# EAGLE_9_X-Piclodio3.net
KiCad netlist of a schematic drawn in EAGLE
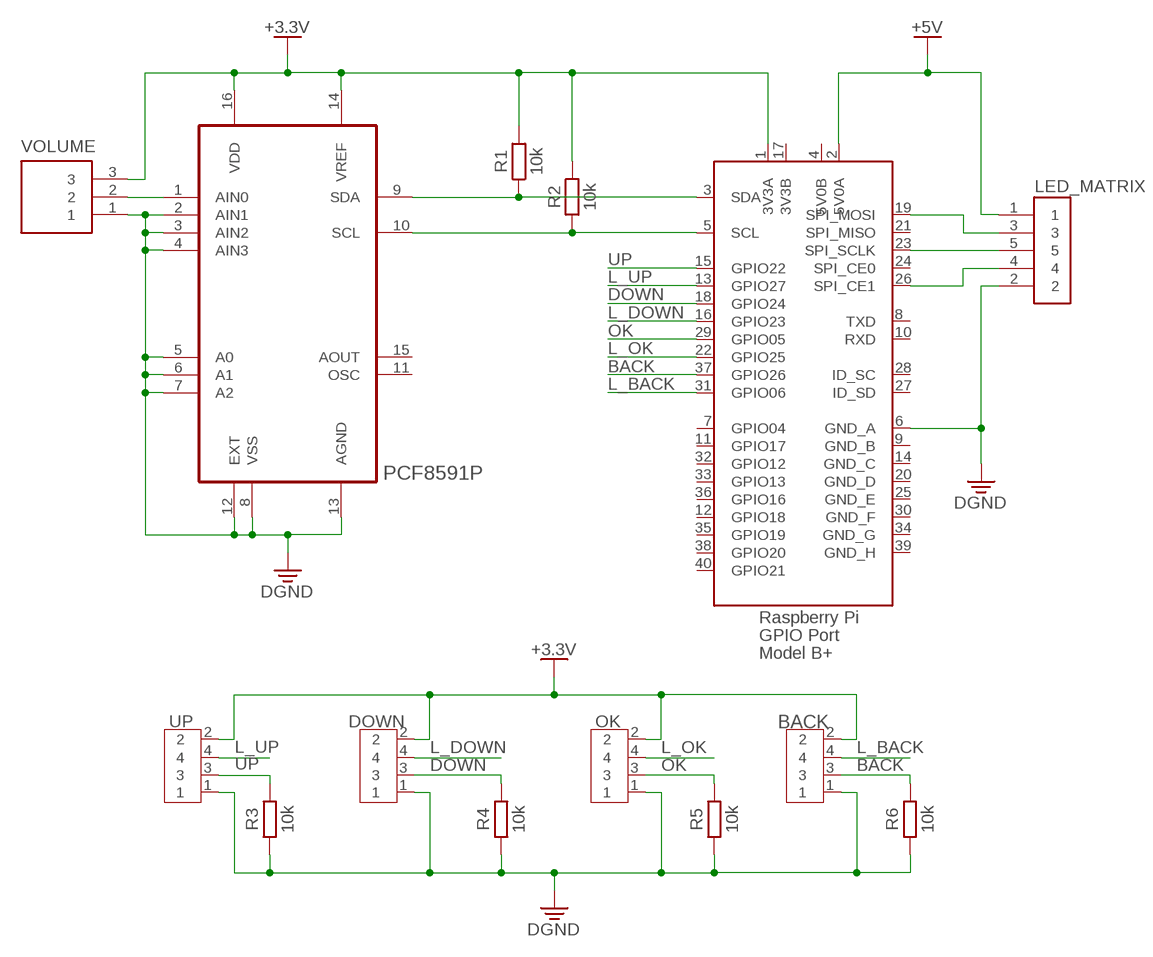
[diagram p0: schematic, sheet 1]

(export (version "E")
  (design (tool "Eeschema 10.0.6"))
  (components
    (comp (ref "BACK")
      (value "3A/250V")
      (footprint "eagle-import:B4B-XH-A")
      (fields (field (name "MANUFACTURER") "JST (XH connector)") (field (name "MPN") "B4B-XH-A"))
      (libsource (lib "eagle-import") (part "B4B-XH-A"))
    )
    (comp (ref "DOWN")
      (value "3A/250V")
      (footprint "eagle-import:B4B-XH-A")
      (fields (field (name "MANUFACTURER") "JST (XH connector)") (field (name "MPN") "B4B-XH-A"))
      (libsource (lib "eagle-import") (part "B4B-XH-A"))
    )
    (comp (ref "LED_MATRIX")
      (value "S5B-XH-A(LF)(SN)")
      (footprint "eagle-import:JST_S5B-XH-A(LF)(SN)")
      (fields (field (name "MANUFACTURER") "JST"))
      (libsource (lib "eagle-import") (part "S5B-XH-A(LF)(SN)"))
    )
    (comp (ref "OK")
      (value "3A/250V")
      (footprint "eagle-import:B4B-XH-A")
      (fields (field (name "MANUFACTURER") "JST (XH connector)") (field (name "MPN") "B4B-XH-A"))
      (libsource (lib "eagle-import") (part "B4B-XH-A"))
    )
    (comp (ref "R1")
      (value "10k")
      (footprint "eagle-import:RESAD1176W63L850D250B")
      (libsource (lib "eagle-import") (part "RAXIAL-11.7MM-PITCH_"))
    )
    (comp (ref "R2")
      (value "10k")
      (footprint "eagle-import:RESAD1176W63L850D250B")
      (libsource (lib "eagle-import") (part "RAXIAL-11.7MM-PITCH_"))
    )
    (comp (ref "R3")
      (value "10k")
      (footprint "eagle-import:RESAD1176W63L850D250B")
      (libsource (lib "eagle-import") (part "RAXIAL-11.7MM-PITCH_"))
    )
    (comp (ref "R4")
      (value "10k")
      (footprint "eagle-import:RESAD1176W63L850D250B")
      (libsource (lib "eagle-import") (part "RAXIAL-11.7MM-PITCH_"))
    )
    (comp (ref "R5")
      (value "10k")
      (footprint "eagle-import:RESAD1176W63L850D250B")
      (libsource (lib "eagle-import") (part "RAXIAL-11.7MM-PITCH_"))
    )
    (comp (ref "R6")
      (value "10k")
      (footprint "eagle-import:RESAD1176W63L850D250B")
      (libsource (lib "eagle-import") (part "RAXIAL-11.7MM-PITCH_"))
    )
    (comp (ref "U2")
      (value "PCF8591P")
      (footprint "eagle-import:DIP254P762X420-16")
      (fields (field (name "MF") "NXP USA"))
      (libsource (lib "eagle-import") (part "PCF8591P"))
    )
    (comp (ref "UP")
      (value "3A/250V")
      (footprint "eagle-import:B4B-XH-A")
      (fields
        (field (name "MANUFACTURER") "JST (XH connector)")
        (field (name "MPN") "B4B-XH-A")
        (field (name "SPICEPREFIX") "E")
      )
      (libsource (lib "eagle-import") (part "B4B-XH-A"))
    )
    (comp (ref "VOLUME")
      (value "S3B-XH-A(LF)(SN)")
      (footprint "eagle-import:JST_S3B-XH-A(LF)(SN)")
      (fields (field (name "MANUFACTURER") "JST"))
      (libsource (lib "eagle-import") (part "S3B-XH-A(LF)(SN)"))
    )
    (comp (ref "X1")
      (value "RASPI_BOARD_B+#_H")
      (footprint "eagle-import:RASPI_BOARD_B+HAT")
      (libsource (lib "eagle-import") (part "RASPI_BOARD_B+#_H"))
    )
  )
  (nets
    (net (code "1") (name "+3.3V") (class "Default")
      (node (ref "BACK") (pin "2") (pinfunction "2_2") (pintype "bidirectional"))
      (node (ref "DOWN") (pin "2") (pinfunction "2_2") (pintype "bidirectional"))
      (node (ref "OK") (pin "2") (pinfunction "2_2") (pintype "bidirectional"))
      (node (ref "R1") (pin "2") (pinfunction "2_2") (pintype "passive"))
      (node (ref "R2") (pin "1") (pinfunction "1_1") (pintype "passive"))
      (node (ref "U2") (pin "14") (pinfunction "VREF_14") (pintype "input"))
      (node (ref "U2") (pin "16") (pinfunction "VDD_16") (pintype "power_in"))
      (node (ref "UP") (pin "2") (pinfunction "2_2") (pintype "bidirectional"))
      (node (ref "VOLUME") (pin "3") (pinfunction "3_3") (pintype "passive"))
      (node (ref "X1") (pin "1") (pinfunction "3V3A_1") (pintype "power_in"))
    )
    (net (code "2") (name "+5V") (class "Default")
      (node (ref "LED_MATRIX") (pin "1") (pinfunction "1_1") (pintype "passive"))
      (node (ref "X1") (pin "2") (pinfunction "5V0A_2") (pintype "power_in"))
    )
    (net (code "3") (name "/BACK") (class "Default")
      (node (ref "BACK") (pin "3") (pinfunction "3_3") (pintype "bidirectional"))
      (node (ref "R6") (pin "2") (pinfunction "2_2") (pintype "passive"))
      (node (ref "X1") (pin "37") (pinfunction "GPIO26_37") (pintype "input"))
    )
    (net (code "4") (name "/DOWN") (class "Default")
      (node (ref "DOWN") (pin "3") (pinfunction "3_3") (pintype "bidirectional"))
      (node (ref "R4") (pin "2") (pinfunction "2_2") (pintype "passive"))
      (node (ref "X1") (pin "18") (pinfunction "GPIO24_18") (pintype "input"))
    )
    (net (code "5") (name "/L_BACK") (class "Default")
      (node (ref "BACK") (pin "4") (pinfunction "4_4") (pintype "bidirectional"))
      (node (ref "X1") (pin "31") (pinfunction "GPIO06_31") (pintype "output"))
    )
    (net (code "6") (name "/L_DOWN") (class "Default")
      (node (ref "DOWN") (pin "4") (pinfunction "4_4") (pintype "bidirectional"))
      (node (ref "X1") (pin "16") (pinfunction "GPIO23_16") (pintype "output"))
    )
    (net (code "7") (name "/L_OK") (class "Default")
      (node (ref "OK") (pin "4") (pinfunction "4_4") (pintype "bidirectional"))
      (node (ref "X1") (pin "22") (pinfunction "GPIO25_22") (pintype "output"))
    )
    (net (code "8") (name "/L_UP") (class "Default")
      (node (ref "UP") (pin "4") (pinfunction "4_4") (pintype "bidirectional"))
      (node (ref "X1") (pin "13") (pinfunction "GPIO27_13") (pintype "output"))
    )
    (net (code "9") (name "/OK") (class "Default")
      (node (ref "OK") (pin "3") (pinfunction "3_3") (pintype "bidirectional"))
      (node (ref "R5") (pin "2") (pinfunction "2_2") (pintype "passive"))
      (node (ref "X1") (pin "29") (pinfunction "GPIO05_29") (pintype "input"))
    )
    (net (code "10") (name "/UP") (class "Default")
      (node (ref "R3") (pin "2") (pinfunction "2_2") (pintype "passive"))
      (node (ref "UP") (pin "3") (pinfunction "3_3") (pintype "bidirectional"))
      (node (ref "X1") (pin "15") (pinfunction "GPIO22_15") (pintype "input"))
    )
    (net (code "11") (name "DGND") (class "Default")
      (node (ref "BACK") (pin "1") (pinfunction "1_1") (pintype "bidirectional"))
      (node (ref "DOWN") (pin "1") (pinfunction "1_1") (pintype "bidirectional"))
      (node (ref "LED_MATRIX") (pin "2") (pinfunction "2_2") (pintype "passive"))
      (node (ref "OK") (pin "1") (pinfunction "1_1") (pintype "bidirectional"))
      (node (ref "R3") (pin "1") (pinfunction "1_1") (pintype "passive"))
      (node (ref "R4") (pin "1") (pinfunction "1_1") (pintype "passive"))
      (node (ref "R5") (pin "1") (pinfunction "1_1") (pintype "passive"))
      (node (ref "R6") (pin "1") (pinfunction "1_1") (pintype "passive"))
      (node (ref "U2") (pin "12") (pinfunction "EXT_12") (pintype "input"))
      (node (ref "U2") (pin "13") (pinfunction "AGND_13") (pintype "power_in"))
      (node (ref "U2") (pin "2") (pinfunction "AIN1_2") (pintype "input"))
      (node (ref "U2") (pin "3") (pinfunction "AIN2_3") (pintype "input"))
      (node (ref "U2") (pin "4") (pinfunction "AIN3_4") (pintype "input"))
      (node (ref "U2") (pin "5") (pinfunction "A0_5") (pintype "input"))
      (node (ref "U2") (pin "6") (pinfunction "A1_6") (pintype "input"))
      (node (ref "U2") (pin "7") (pinfunction "A2_7") (pintype "input"))
      (node (ref "U2") (pin "8") (pinfunction "VSS_8") (pintype "input"))
      (node (ref "UP") (pin "1") (pinfunction "1_1") (pintype "bidirectional"))
      (node (ref "VOLUME") (pin "1") (pinfunction "1_1") (pintype "passive"))
      (node (ref "X1") (pin "6") (pinfunction "GND_A_6") (pintype "power_in"))
    )
    (net (code "12") (name "Net-(U2-AIN0)") (class "Default")
      (node (ref "U2") (pin "1") (pinfunction "AIN0_1") (pintype "input"))
      (node (ref "VOLUME") (pin "2") (pinfunction "2_2") (pintype "passive"))
    )
    (net (code "13") (name "Net-(U2-SCL)") (class "Default")
      (node (ref "R2") (pin "2") (pinfunction "2_2") (pintype "passive"))
      (node (ref "U2") (pin "10") (pinfunction "SCL_10") (pintype "input"))
      (node (ref "X1") (pin "5") (pinfunction "SCL_5") (pintype "bidirectional"))
    )
    (net (code "14") (name "Net-(U2-SDA)") (class "Default")
      (node (ref "R1") (pin "1") (pinfunction "1_1") (pintype "passive"))
      (node (ref "U2") (pin "9") (pinfunction "SDA_9") (pintype "bidirectional"))
      (node (ref "X1") (pin "3") (pinfunction "SDA_3") (pintype "bidirectional"))
    )
    (net (code "15") (name "Net-(X1-SPI_CE1)") (class "Default")
      (node (ref "LED_MATRIX") (pin "4") (pinfunction "4_4") (pintype "passive"))
      (node (ref "X1") (pin "26") (pinfunction "SPI_CE1_26") (pintype "bidirectional"))
    )
    (net (code "16") (name "Net-(X1-SPI_MOSI)") (class "Default")
      (node (ref "LED_MATRIX") (pin "3") (pinfunction "3_3") (pintype "passive"))
      (node (ref "X1") (pin "19") (pinfunction "SPI_MOSI_19") (pintype "bidirectional"))
    )
    (net (code "17") (name "Net-(X1-SPI_SCLK)") (class "Default")
      (node (ref "LED_MATRIX") (pin "5") (pinfunction "5_5") (pintype "passive"))
      (node (ref "X1") (pin "23") (pinfunction "SPI_SCLK_23") (pintype "bidirectional"))
    )
    (net (code "18") (name "unconnected-(U2-AOUT-Pad15)") (class "Default")
      (node (ref "U2") (pin "15") (pinfunction "AOUT_15") (pintype "output"))
    )
    (net (code "19") (name "unconnected-(U2-OSC-Pad11)") (class "Default")
      (node (ref "U2") (pin "11") (pinfunction "OSC_11") (pintype "bidirectional"))
    )
    (net (code "20") (name "unconnected-(X1-3V3B-Pad17)") (class "Default")
      (node (ref "X1") (pin "17") (pinfunction "3V3B_17") (pintype "no_connect"))
    )
    (net (code "21") (name "unconnected-(X1-5V0B-Pad4)") (class "Default")
      (node (ref "X1") (pin "4") (pinfunction "5V0B_4") (pintype "no_connect"))
    )
    (net (code "22") (name "unconnected-(X1-GND_B-Pad9)") (class "Default")
      (node (ref "X1") (pin "9") (pinfunction "GND_B_9") (pintype "no_connect"))
    )
    (net (code "23") (name "unconnected-(X1-GND_C-Pad14)") (class "Default")
      (node (ref "X1") (pin "14") (pinfunction "GND_C_14") (pintype "no_connect"))
    )
    (net (code "24") (name "unconnected-(X1-GND_D-Pad20)") (class "Default")
      (node (ref "X1") (pin "20") (pinfunction "GND_D_20") (pintype "no_connect"))
    )
    (net (code "25") (name "unconnected-(X1-GND_E-Pad25)") (class "Default")
      (node (ref "X1") (pin "25") (pinfunction "GND_E_25") (pintype "no_connect"))
    )
    (net (code "26") (name "unconnected-(X1-GND_F-Pad30)") (class "Default")
      (node (ref "X1") (pin "30") (pinfunction "GND_F_30") (pintype "no_connect"))
    )
    (net (code "27") (name "unconnected-(X1-GND_G-Pad34)") (class "Default")
      (node (ref "X1") (pin "34") (pinfunction "GND_G_34") (pintype "no_connect"))
    )
    (net (code "28") (name "unconnected-(X1-GND_H-Pad39)") (class "Default")
      (node (ref "X1") (pin "39") (pinfunction "GND_H_39") (pintype "no_connect"))
    )
    (net (code "29") (name "unconnected-(X1-GPIO04-Pad7)") (class "Default")
      (node (ref "X1") (pin "7") (pinfunction "GPIO04_7") (pintype "no_connect"))
    )
    (net (code "30") (name "unconnected-(X1-GPIO12-Pad32)") (class "Default")
      (node (ref "X1") (pin "32") (pinfunction "GPIO12_32") (pintype "no_connect"))
    )
    (net (code "31") (name "unconnected-(X1-GPIO13-Pad33)") (class "Default")
      (node (ref "X1") (pin "33") (pinfunction "GPIO13_33") (pintype "no_connect"))
    )
    (net (code "32") (name "unconnected-(X1-GPIO16-Pad36)") (class "Default")
      (node (ref "X1") (pin "36") (pinfunction "GPIO16_36") (pintype "no_connect"))
    )
    (net (code "33") (name "unconnected-(X1-GPIO17-Pad11)") (class "Default")
      (node (ref "X1") (pin "11") (pinfunction "GPIO17_11") (pintype "no_connect"))
    )
    (net (code "34") (name "unconnected-(X1-GPIO18-Pad12)") (class "Default")
      (node (ref "X1") (pin "12") (pinfunction "GPIO18_12") (pintype "no_connect"))
    )
    (net (code "35") (name "unconnected-(X1-GPIO19-Pad35)") (class "Default")
      (node (ref "X1") (pin "35") (pinfunction "GPIO19_35") (pintype "no_connect"))
    )
    (net (code "36") (name "unconnected-(X1-GPIO20-Pad38)") (class "Default")
      (node (ref "X1") (pin "38") (pinfunction "GPIO20_38") (pintype "no_connect"))
    )
    (net (code "37") (name "unconnected-(X1-GPIO21-Pad40)") (class "Default")
      (node (ref "X1") (pin "40") (pinfunction "GPIO21_40") (pintype "no_connect"))
    )
    (net (code "38") (name "unconnected-(X1-ID_SC-Pad28)") (class "Default")
      (node (ref "X1") (pin "28") (pinfunction "ID_SC_28") (pintype "no_connect"))
    )
    (net (code "39") (name "unconnected-(X1-ID_SD-Pad27)") (class "Default")
      (node (ref "X1") (pin "27") (pinfunction "ID_SD_27") (pintype "no_connect"))
    )
    (net (code "40") (name "unconnected-(X1-RXD-Pad10)") (class "Default")
      (node (ref "X1") (pin "10") (pinfunction "RXD_10") (pintype "no_connect"))
    )
    (net (code "41") (name "unconnected-(X1-SPI_CE0-Pad24)") (class "Default")
      (node (ref "X1") (pin "24") (pinfunction "SPI_CE0_24") (pintype "no_connect"))
    )
    (net (code "42") (name "unconnected-(X1-SPI_MISO-Pad21)") (class "Default")
      (node (ref "X1") (pin "21") (pinfunction "SPI_MISO_21") (pintype "bidirectional"))
    )
    (net (code "43") (name "unconnected-(X1-TXD-Pad8)") (class "Default")
      (node (ref "X1") (pin "8") (pinfunction "TXD_8") (pintype "no_connect"))
    )
  )
)
